# Candunio.net
KiCad netlist of a schematic drawn in Altium Designer
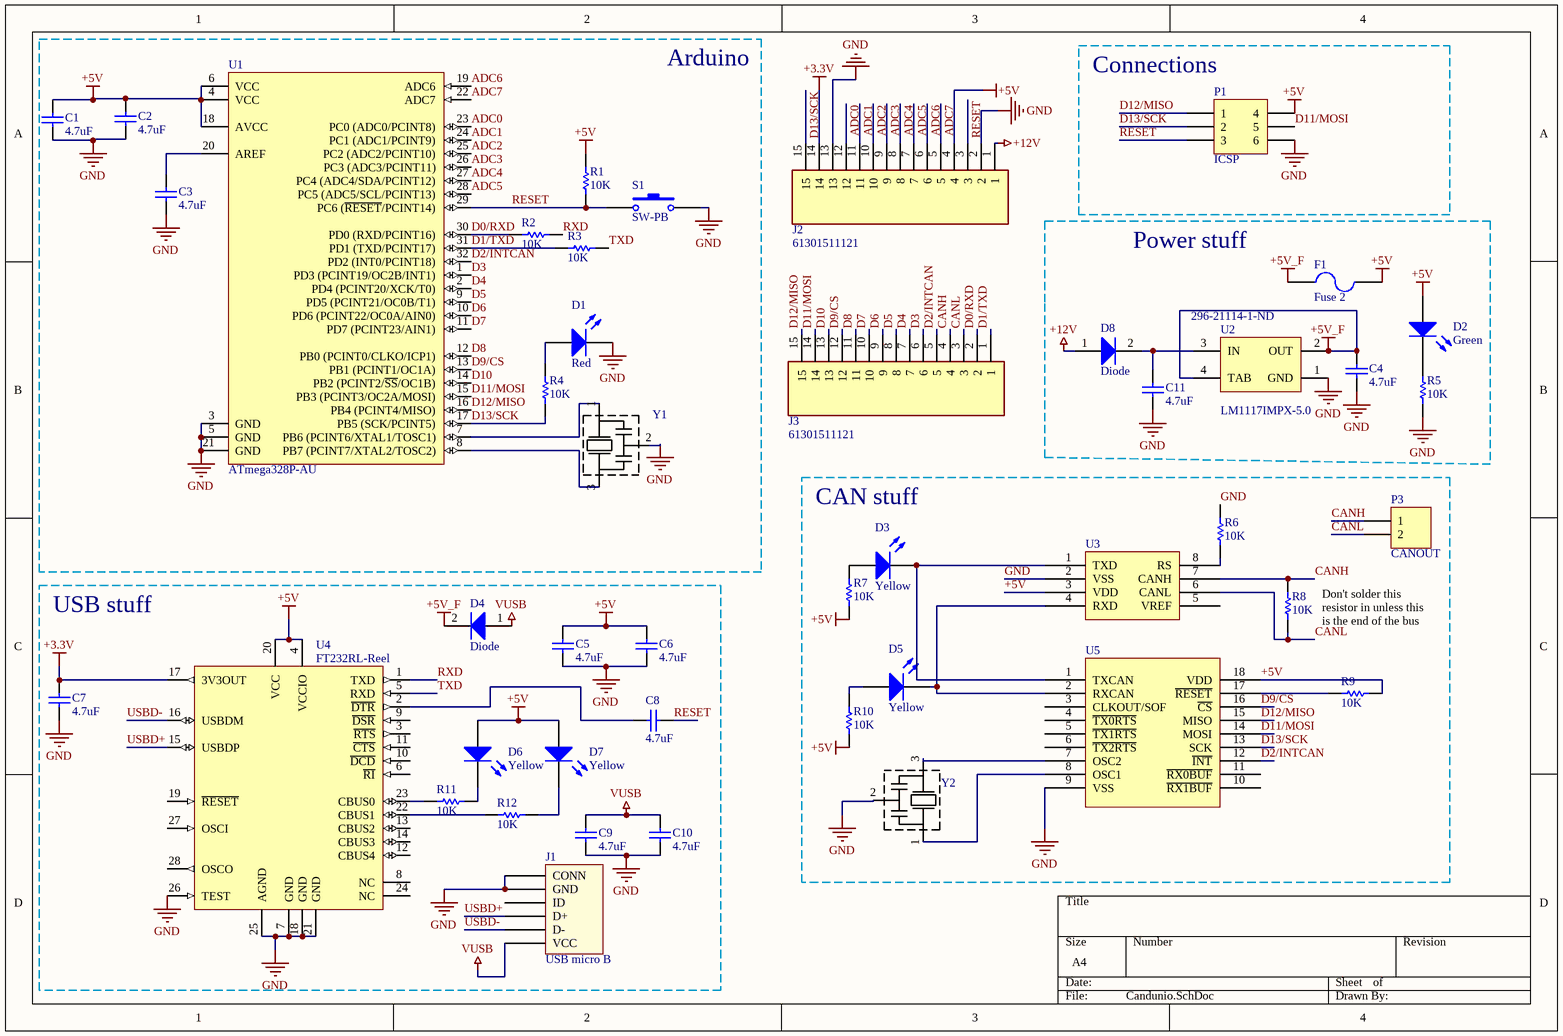
[diagram p0: Candunio.SchDoc]

(export (version "E")
  (design (tool "Eeschema 10.0.6"))
  (components
    (comp (ref "C1")
      (value "4.7uF")
      (footprint "CAPC3216X170N")
      (description "Capacitor (Semiconductor SIM Model)")
      (fields
        (field (name "MANUFACTURER") "Murata")
        (field (name "MANUFACTURER PART NUMBER") "GRM31MR71H105KA88L")
        (field (name "PUBLISHER") "Altium Limited")
      )
      (libsource (lib "Candunio") (part "Cap Semi"))
    )
    (comp (ref "C2")
      (value "4.7uF")
      (footprint "CAPC3216X170N")
      (description "Capacitor (Semiconductor SIM Model)")
      (fields
        (field (name "MANUFACTURER") "Murata")
        (field (name "MANUFACTURER PART NUMBER") "GRM31MR71H105KA88L")
        (field (name "PUBLISHER") "Altium Limited")
      )
      (libsource (lib "Candunio") (part "Cap Semi"))
    )
    (comp (ref "C3")
      (value "4.7uF")
      (footprint "CAPC3216X170N")
      (description "Capacitor (Semiconductor SIM Model)")
      (fields
        (field (name "MANUFACTURER") "Murata")
        (field (name "MANUFACTURER PART NUMBER") "GRM31MR71H105KA88L")
        (field (name "PUBLISHER") "Altium Limited")
      )
      (libsource (lib "Candunio") (part "Cap Semi"))
    )
    (comp (ref "C4")
      (value "4.7uF")
      (footprint "CAPC3216X170N")
      (description "Capacitor (Semiconductor SIM Model)")
      (fields
        (field (name "MANUFACTURER") "Murata")
        (field (name "MANUFACTURER PART NUMBER") "GRM31MR71H105KA88L")
        (field (name "PUBLISHER") "Altium Limited")
      )
      (libsource (lib "Candunio") (part "Cap Semi"))
    )
    (comp (ref "C5")
      (value "4.7uF")
      (footprint "CAPC3216X170N")
      (description "Capacitor (Semiconductor SIM Model)")
      (fields
        (field (name "MANUFACTURER") "Murata")
        (field (name "MANUFACTURER PART NUMBER") "GRM31MR71H105KA88L")
        (field (name "PUBLISHER") "Altium Limited")
      )
      (libsource (lib "Candunio") (part "Cap Semi"))
    )
    (comp (ref "C6")
      (value "4.7uF")
      (footprint "CAPC3216X170N")
      (description "Capacitor (Semiconductor SIM Model)")
      (fields
        (field (name "MANUFACTURER") "Murata")
        (field (name "MANUFACTURER PART NUMBER") "GRM31MR71H105KA88L")
        (field (name "PUBLISHER") "Altium Limited")
      )
      (libsource (lib "Candunio") (part "Cap Semi"))
    )
    (comp (ref "C7")
      (value "4.7uF")
      (footprint "CAPC3216X170N")
      (description "Capacitor (Semiconductor SIM Model)")
      (fields
        (field (name "MANUFACTURER") "Murata")
        (field (name "MANUFACTURER PART NUMBER") "GRM31MR71H105KA88L")
        (field (name "PUBLISHER") "Altium Limited")
      )
      (libsource (lib "Candunio") (part "Cap Semi"))
    )
    (comp (ref "C8")
      (value "4.7uF")
      (footprint "CAPC3216X170N")
      (description "Capacitor (Semiconductor SIM Model)")
      (fields
        (field (name "MANUFACTURER") "Murata")
        (field (name "MANUFACTURER PART NUMBER") "GRM31MR71H105KA88L")
        (field (name "PUBLISHER") "Altium Limited")
      )
      (libsource (lib "Candunio") (part "Cap Semi"))
    )
    (comp (ref "C9")
      (value "4.7uF")
      (footprint "CAPC3216X170N")
      (description "Capacitor (Semiconductor SIM Model)")
      (fields
        (field (name "MANUFACTURER") "Murata")
        (field (name "MANUFACTURER PART NUMBER") "GRM31MR71H105KA88L")
        (field (name "PUBLISHER") "Altium Limited")
      )
      (libsource (lib "Candunio") (part "Cap Semi"))
    )
    (comp (ref "C10")
      (value "4.7uF")
      (footprint "CAPC3216X170N")
      (description "Capacitor (Semiconductor SIM Model)")
      (fields
        (field (name "MANUFACTURER") "Murata")
        (field (name "MANUFACTURER PART NUMBER") "GRM31MR71H105KA88L")
        (field (name "PUBLISHER") "Altium Limited")
      )
      (libsource (lib "Candunio") (part "Cap Semi"))
    )
    (comp (ref "C11")
      (value "4.7uF")
      (footprint "CAPC3216X170N")
      (description "Capacitor (Semiconductor SIM Model)")
      (fields
        (field (name "MANUFACTURER") "Murata")
        (field (name "MANUFACTURER PART NUMBER") "GRM31MR71H105KA88L")
        (field (name "PUBLISHER") "Altium Limited")
      )
      (libsource (lib "Candunio") (part "Cap Semi"))
    )
    (comp (ref "D1")
      (value "Red")
      (footprint "LEDC3216X120NRED")
      (description "Typical RED, GREEN, YELLOW, AMBER GaAs LED")
      (fields
        (field (name "MANUFACTURER") "Broadcom Avago")
        (field (name "MANUFACTURER PART NUMBER") "HSMY-C150")
        (field (name "PUBLISHER") "Altium Limited")
      )
      (libsource (lib "Candunio") (part "LED2_2"))
    )
    (comp (ref "D2")
      (value "Green")
      (footprint "LEDC3216X120NGRN")
      (description "Typical RED, GREEN, YELLOW, AMBER GaAs LED")
      (fields
        (field (name "MANUFACTURER") "Broadcom Avago")
        (field (name "MANUFACTURER PART NUMBER") "HSMG-C150")
        (field (name "PUBLISHER") "Altium Limited")
      )
      (libsource (lib "Candunio") (part "LED2"))
    )
    (comp (ref "D3")
      (value "Yellow")
      (footprint "LEDC3216X120NYEL")
      (description "Typical RED, GREEN, YELLOW, AMBER GaAs LED")
      (fields
        (field (name "MANUFACTURER") "Broadcom Avago")
        (field (name "MANUFACTURER PART NUMBER") "HSMY-C150")
        (field (name "PUBLISHER") "Altium Limited")
      )
      (libsource (lib "Candunio") (part "LED2_1"))
    )
    (comp (ref "D4")
      (value "Diode")
      (footprint "DO-220AA")
      (description "Default Diode")
      (fields (field (name "PUBLISHER") "Altium Limited"))
      (libsource (lib "Candunio") (part "Diode"))
    )
    (comp (ref "D5")
      (value "Yellow")
      (footprint "LEDC3216X120NYEL")
      (description "Typical RED, GREEN, YELLOW, AMBER GaAs LED")
      (fields
        (field (name "MANUFACTURER") "Broadcom Avago")
        (field (name "MANUFACTURER PART NUMBER") "HSMY-C150")
        (field (name "PUBLISHER") "Altium Limited")
      )
      (libsource (lib "Candunio") (part "LED2_1"))
    )
    (comp (ref "D6")
      (value "Yellow")
      (footprint "LEDC3216X120NYEL")
      (description "Typical RED, GREEN, YELLOW, AMBER GaAs LED")
      (fields
        (field (name "MANUFACTURER") "Broadcom Avago")
        (field (name "MANUFACTURER PART NUMBER") "HSMY-C150")
        (field (name "PUBLISHER") "Altium Limited")
      )
      (libsource (lib "Candunio") (part "LED2_1"))
    )
    (comp (ref "D7")
      (value "Yellow")
      (footprint "LEDC3216X120NYEL")
      (description "Typical RED, GREEN, YELLOW, AMBER GaAs LED")
      (fields
        (field (name "MANUFACTURER") "Broadcom Avago")
        (field (name "MANUFACTURER PART NUMBER") "HSMY-C150")
        (field (name "PUBLISHER") "Altium Limited")
      )
      (libsource (lib "Candunio") (part "LED2_1"))
    )
    (comp (ref "D8")
      (value "Diode")
      (footprint "DO-220AA")
      (description "Default Diode")
      (fields (field (name "PUBLISHER") "Altium Limited"))
      (libsource (lib "Candunio") (part "Diode"))
    )
    (comp (ref "F1")
      (value "Fuse 2")
      (footprint "FUSC4632X85N")
      (description "Fuse")
      (fields
        (field (name "PART NUMBER") "MF-MSMF050-2")
        (field (name "MANUFACTURER") "Bourns")
        (field (name "PUBLISHER") "Altium Limited")
      )
      (libsource (lib "Candunio") (part "Fuse 2"))
    )
    (comp (ref "J1")
      (value "USB micro B")
      (footprint "1050170001")
      (description "CONN SM TH USB MICRO MODIFIED FOR DRILL")
      (fields (field (name "PART NUMBER") "WM1399CT-ND"))
      (libsource (lib "electronpowered") (part "1050170001"))
    )
    (comp (ref "J2")
      (value "61301511121")
      (footprint "SamacSys:HDRV15W95P0X254_1X15_3810X254X854P")
      (description "Connector")
      (fields
        (field (name "MOUSER PART NUMBER") "710-61301511121")
        (field (name "RS PART NUMBER") "8281623P")
      )
      (libsource (lib "*") (part "61301511121"))
    )
    (comp (ref "J3")
      (value "61301511121")
      (footprint "SamacSys:HDRV15W95P0X254_1X15_3810X254X854P")
      (description "Connector")
      (fields
        (field (name "MOUSER PART NUMBER") "710-61301511121")
        (field (name "RS PART NUMBER") "8281623P")
      )
      (libsource (lib "*") (part "61301511121"))
    )
    (comp (ref "P1")
      (value "ICSP")
      (footprint "Pin Header 2x3 TH Pitch 2.54mm")
      (description "Header, 3-Pin, Dual row")
      (fields (field (name "PUBLISHER") "Altium Limited"))
      (libsource (lib "Candunio") (part "Header 3X2A"))
    )
    (comp (ref "P3")
      (value "CANOUT")
      (footprint "Pin Header 1x2 TH Pitch 2.54mm")
      (description "Header, 2-Pin")
      (fields (field (name "PUBLISHER") "Altium Limited"))
      (libsource (lib "Candunio") (part "Header 2"))
    )
    (comp (ref "R1")
      (value "10K")
      (footprint "RESC3216X60N")
      (description "Resistor")
      (fields
        (field (name "MANUFACTURER") "Stackpole Electronics")
        (field (name "MANUFACTURER PART NUMBER") "RNCP1206FTD1K00")
      )
      (libsource (lib "Candunio") (part "Res1"))
    )
    (comp (ref "R2")
      (value "10K")
      (footprint "RESC3216X60N")
      (description "Resistor")
      (fields
        (field (name "MANUFACTURER") "Stackpole Electronics")
        (field (name "MANUFACTURER PART NUMBER") "RNCP1206FTD1K00")
      )
      (libsource (lib "Candunio") (part "Res1"))
    )
    (comp (ref "R3")
      (value "10K")
      (footprint "RESC3216X60N")
      (description "Resistor")
      (fields
        (field (name "MANUFACTURER") "Stackpole Electronics")
        (field (name "MANUFACTURER PART NUMBER") "RNCP1206FTD1K00")
      )
      (libsource (lib "Candunio") (part "Res1"))
    )
    (comp (ref "R4")
      (value "10K")
      (footprint "RESC3216X60N")
      (description "Resistor")
      (fields
        (field (name "MANUFACTURER") "Stackpole Electronics")
        (field (name "MANUFACTURER PART NUMBER") "RNCP1206FTD1K00")
      )
      (libsource (lib "Candunio") (part "Res1"))
    )
    (comp (ref "R5")
      (value "10K")
      (footprint "RESC3216X60N")
      (description "Resistor")
      (fields
        (field (name "MANUFACTURER") "Stackpole Electronics")
        (field (name "MANUFACTURER PART NUMBER") "RNCP1206FTD1K00")
      )
      (libsource (lib "Candunio") (part "Res1"))
    )
    (comp (ref "R6")
      (value "10K")
      (footprint "RESC3216X60N")
      (description "Resistor")
      (fields
        (field (name "MANUFACTURER") "Stackpole Electronics")
        (field (name "MANUFACTURER PART NUMBER") "RNCP1206FTD1K00")
      )
      (libsource (lib "Candunio") (part "Res1"))
    )
    (comp (ref "R7")
      (value "10K")
      (footprint "RESC3216X60N")
      (description "Resistor")
      (fields
        (field (name "MANUFACTURER") "Stackpole Electronics")
        (field (name "MANUFACTURER PART NUMBER") "RNCP1206FTD1K00")
      )
      (libsource (lib "Candunio") (part "Res1"))
    )
    (comp (ref "R8")
      (value "10K")
      (footprint "RESC3216X60N")
      (description "Resistor")
      (fields
        (field (name "MANUFACTURER") "Stackpole Electronics")
        (field (name "MANUFACTURER PART NUMBER") "RNCP1206FTD1K00")
      )
      (libsource (lib "Candunio") (part "Res1"))
    )
    (comp (ref "R9")
      (value "10K")
      (footprint "RESC3216X60N")
      (description "Resistor")
      (fields
        (field (name "MANUFACTURER") "Stackpole Electronics")
        (field (name "MANUFACTURER PART NUMBER") "RNCP1206FTD1K00")
      )
      (libsource (lib "Candunio") (part "Res1"))
    )
    (comp (ref "R10")
      (value "10K")
      (footprint "RESC3216X60N")
      (description "Resistor")
      (fields
        (field (name "MANUFACTURER") "Stackpole Electronics")
        (field (name "MANUFACTURER PART NUMBER") "RNCP1206FTD1K00")
      )
      (libsource (lib "Candunio") (part "Res1"))
    )
    (comp (ref "R11")
      (value "10K")
      (footprint "RESC3216X60N")
      (description "Resistor")
      (fields
        (field (name "MANUFACTURER") "Stackpole Electronics")
        (field (name "MANUFACTURER PART NUMBER") "RNCP1206FTD1K00")
      )
      (libsource (lib "Candunio") (part "Res1"))
    )
    (comp (ref "R12")
      (value "10K")
      (footprint "RESC3216X60N")
      (description "Resistor")
      (fields
        (field (name "MANUFACTURER") "Stackpole Electronics")
        (field (name "MANUFACTURER PART NUMBER") "RNCP1206FTD1K00")
      )
      (libsource (lib "Candunio") (part "Res1"))
    )
    (comp (ref "S1")
      (value "SW-PB")
      (footprint "SMDswitch_1206")
      (description "Switch")
      (fields
        (field (name "MANUFACTURER") "ITT C&K")
        (field (name "MANUFACTURER PART NUMBER") "KXT331LHS")
        (field (name "PUBLISHER") "Altium Limited")
      )
      (libsource (lib "Candunio") (part "SW-PB"))
    )
    (comp (ref "U1")
      (value "ATmega328P-AU")
      (footprint "QFP80P900X900X120-32N")
      (fields (field (name "PUBLISHER") "Altium Limited"))
      (libsource (lib "Candunio") (part "ATmega328P-AU"))
    )
    (comp (ref "U2")
      (value "LM1117IMPX-5.0")
      (footprint "SOT230P700X180-4N")
      (description "800mA Low-Dropout Linear Regulator, 4-pin SOT-223")
      (fields
        (field (name "PARTNUMBER") "LM1117IMPX-5.0/NOPBCT-ND")
        (field (name "MANUFACTURER") "National Semiconductor")
        (field (name "SUPPLIER PART NUMBER") "296-21114-1-ND")
        (field (name "PUBLISHER") "Altium Limited")
      )
      (libsource (lib "NSC LDO") (part "LM1117IMPX-5.0"))
    )
    (comp (ref "U3")
      (value "MCP2551-E/SN")
      (footprint "SOIC127P600X175-8N")
      (description "SOIC")
      (libsource (lib "Candunio") (part "MCP2551-E/SN"))
    )
    (comp (ref "U4")
      (value "FT232RL-Reel")
      (footprint "SOP65P780X200-28N")
      (description "USB UART Asynchronous Serial Data Transfer Chip, SSOP-28, Tape and Reel")
      (fields
        (field (name "MANUFACTURER") "FTDI")
        (field (name "MANUFACTURER PART NUMBER") "FT232RL-REEL")
        (field (name "PUBLISHER") "Altium Limited")
      )
      (libsource (lib "FTDI Communication UART") (part "FT232RL-Reel"))
    )
    (comp (ref "U5")
      (value "MCP2515-E/ST")
      (footprint "SOIC127P1030X265-18N")
      (description "SOIC")
      (libsource (lib "Candunio") (part "MCP2515-E/ST"))
    )
    (comp (ref "Y1")
      (value "CSTCE16M0V53-R0")
      (footprint "CSTCE_G")
      (fields
        (field (name "MANUFACTURER") "Murata")
        (field (name "MANUFACTURER PART NUMBER") "CSTCE16M0V53C-R0")
        (field (name "TOLERANCE") "0.5%")
      )
      (libsource (lib "Candunio") (part "CSTCE16M0V53-R0"))
    )
    (comp (ref "Y2")
      (value "CSTCE16M0V53-R0")
      (footprint "CSTCE_G")
      (fields
        (field (name "MANUFACTURER") "Murata")
        (field (name "MANUFACTURER PART NUMBER") "CSTCE16M0V53C-R0")
        (field (name "TOLERANCE") "0.5%")
      )
      (libsource (lib "Candunio") (part "CSTCE16M0V53-R0"))
    )
  )
  (nets
    (net (code "1") (name "+3.3V") (class "Default")
      (node (ref "C7") (pin "2") (pinfunction "2_2") (pintype "passive"))
      (node (ref "J2") (pin "14") (pinfunction "14_14") (pintype "passive"))
      (node (ref "U4") (pin "17") (pinfunction "3V3OUT_17") (pintype "output"))
    )
    (net (code "2") (name "+5V") (class "Default")
      (node (ref "C1") (pin "1") (pinfunction "1_1") (pintype "passive"))
      (node (ref "C2") (pin "2") (pinfunction "2_2") (pintype "passive"))
      (node (ref "C5") (pin "2") (pinfunction "2_2") (pintype "passive"))
      (node (ref "C6") (pin "2") (pinfunction "2_2") (pintype "passive"))
      (node (ref "D2") (pin "2") (pinfunction "A_2") (pintype "passive"))
      (node (ref "D6") (pin "2") (pinfunction "A_2") (pintype "passive"))
      (node (ref "D7") (pin "2") (pinfunction "A_2") (pintype "passive"))
      (node (ref "F1") (pin "2") (pinfunction "2_2") (pintype "passive"))
      (node (ref "J2") (pin "4") (pinfunction "4_4") (pintype "passive"))
      (node (ref "P1") (pin "4") (pinfunction "4_4") (pintype "passive"))
      (node (ref "R1") (pin "1") (pinfunction "1_1") (pintype "passive"))
      (node (ref "R10") (pin "2") (pinfunction "2_2") (pintype "passive"))
      (node (ref "R7") (pin "1") (pinfunction "1_1") (pintype "passive"))
      (node (ref "R9") (pin "2") (pinfunction "2_2") (pintype "passive"))
      (node (ref "U1") (pin "18") (pinfunction "AVCC_18") (pintype "power_in"))
      (node (ref "U1") (pin "4") (pinfunction "VCC_4") (pintype "power_in"))
      (node (ref "U1") (pin "6") (pinfunction "VCC_6") (pintype "power_in"))
      (node (ref "U3") (pin "3") (pinfunction "VDD_3") (pintype "passive"))
      (node (ref "U4") (pin "20") (pinfunction "VCC_20") (pintype "power_in"))
      (node (ref "U4") (pin "4") (pinfunction "VCCIO_4") (pintype "power_in"))
      (node (ref "U5") (pin "18") (pinfunction "VDD_18") (pintype "passive"))
    )
    (net (code "3") (name "+5V_F") (class "Default")
      (node (ref "C4") (pin "2") (pinfunction "2_2") (pintype "passive"))
      (node (ref "D4") (pin "2") (pinfunction "K_2") (pintype "passive"))
      (node (ref "F1") (pin "1") (pinfunction "1_1") (pintype "passive"))
      (node (ref "U2") (pin "2") (pinfunction "OUT_2") (pintype "power_in"))
      (node (ref "U2") (pin "4") (pinfunction "TAB_4") (pintype "power_in"))
    )
    (net (code "4") (name "+12V") (class "Default")
      (node (ref "D8") (pin "1") (pinfunction "A_1") (pintype "passive"))
      (node (ref "J2") (pin "1") (pinfunction "1_1") (pintype "passive"))
    )
    (net (code "5") (name "/ADC0") (class "Default")
      (node (ref "J2") (pin "12") (pinfunction "12_12") (pintype "passive"))
      (node (ref "U1") (pin "23") (pinfunction "PC0_(ADC0/PCINT8)_23") (pintype "bidirectional"))
    )
    (net (code "6") (name "/ADC1") (class "Default")
      (node (ref "J2") (pin "11") (pinfunction "11_11") (pintype "passive"))
      (node (ref "U1") (pin "24") (pinfunction "PC1_(ADC1/PCINT9)_24") (pintype "bidirectional"))
    )
    (net (code "7") (name "/ADC2") (class "Default")
      (node (ref "J2") (pin "10") (pinfunction "10_10") (pintype "passive"))
      (node (ref "U1") (pin "25") (pinfunction "PC2_(ADC2/PCINT10)_25") (pintype "bidirectional"))
    )
    (net (code "8") (name "/ADC3") (class "Default")
      (node (ref "J2") (pin "9") (pinfunction "9_9") (pintype "passive"))
      (node (ref "U1") (pin "26") (pinfunction "PC3_(ADC3/PCINT11)_26") (pintype "bidirectional"))
    )
    (net (code "9") (name "/ADC4") (class "Default")
      (node (ref "J2") (pin "8") (pinfunction "8_8") (pintype "passive"))
      (node (ref "U1") (pin "27") (pinfunction "PC4_(ADC4/SDA/PCINT12)_27") (pintype "bidirectional"))
    )
    (net (code "10") (name "/ADC5") (class "Default")
      (node (ref "J2") (pin "7") (pinfunction "7_7") (pintype "passive"))
      (node (ref "U1") (pin "28") (pinfunction "PC5_(ADC5/SCL/PCINT13)_28") (pintype "bidirectional"))
    )
    (net (code "11") (name "/ADC6") (class "Default")
      (node (ref "J2") (pin "6") (pinfunction "6_6") (pintype "passive"))
      (node (ref "U1") (pin "19") (pinfunction "ADC6_19") (pintype "input"))
    )
    (net (code "12") (name "/ADC7") (class "Default")
      (node (ref "J2") (pin "5") (pinfunction "5_5") (pintype "passive"))
      (node (ref "U1") (pin "22") (pinfunction "ADC7_22") (pintype "input"))
    )
    (net (code "13") (name "/CANH") (class "Default")
      (node (ref "J3") (pin "4") (pinfunction "4_4") (pintype "passive"))
      (node (ref "P3") (pin "1") (pinfunction "1_1") (pintype "passive"))
      (node (ref "R8") (pin "1") (pinfunction "1_1") (pintype "passive"))
      (node (ref "U3") (pin "7") (pinfunction "CANH_7") (pintype "passive"))
    )
    (net (code "14") (name "/CANL") (class "Default")
      (node (ref "J3") (pin "3") (pinfunction "3_3") (pintype "passive"))
      (node (ref "P3") (pin "2") (pinfunction "2_2") (pintype "passive"))
      (node (ref "R8") (pin "2") (pinfunction "2_2") (pintype "passive"))
      (node (ref "U3") (pin "6") (pinfunction "CANL_6") (pintype "passive"))
    )
    (net (code "15") (name "/D0{slash}RXD") (class "Default")
      (node (ref "J3") (pin "2") (pinfunction "2_2") (pintype "passive"))
      (node (ref "R2") (pin "1") (pinfunction "1_1") (pintype "passive"))
      (node (ref "U1") (pin "30") (pinfunction "PD0_(RXD/PCINT16)_30") (pintype "bidirectional"))
    )
    (net (code "16") (name "/D1{slash}TXD") (class "Default")
      (node (ref "J3") (pin "1") (pinfunction "1_1") (pintype "passive"))
      (node (ref "R3") (pin "1") (pinfunction "1_1") (pintype "passive"))
      (node (ref "U1") (pin "31") (pinfunction "PD1_(TXD/PCINT17)_31") (pintype "bidirectional"))
    )
    (net (code "17") (name "/D2{slash}INTCAN") (class "Default")
      (node (ref "J3") (pin "5") (pinfunction "5_5") (pintype "passive"))
      (node (ref "U1") (pin "32") (pinfunction "PD2_(INT0/PCINT18)_32") (pintype "bidirectional"))
      (node (ref "U5") (pin "12") (pinfunction "~{INT}_12") (pintype "passive"))
    )
    (net (code "18") (name "/D3") (class "Default")
      (node (ref "J3") (pin "6") (pinfunction "6_6") (pintype "passive"))
      (node (ref "U1") (pin "1") (pinfunction "PD3_(PCINT19/OC2B/INT1)_1") (pintype "bidirectional"))
    )
    (net (code "19") (name "/D4") (class "Default")
      (node (ref "J3") (pin "7") (pinfunction "7_7") (pintype "passive"))
      (node (ref "U1") (pin "2") (pinfunction "PD4_(PCINT20/XCK/T0)_2") (pintype "bidirectional"))
    )
    (net (code "20") (name "/D5") (class "Default")
      (node (ref "J3") (pin "8") (pinfunction "8_8") (pintype "passive"))
      (node (ref "U1") (pin "9") (pinfunction "PD5_(PCINT21/OC0B/T1)_9") (pintype "bidirectional"))
    )
    (net (code "21") (name "/D6") (class "Default")
      (node (ref "J3") (pin "9") (pinfunction "9_9") (pintype "passive"))
      (node (ref "U1") (pin "10") (pinfunction "PD6_(PCINT22/OC0A/AIN0)_10") (pintype "bidirectional"))
    )
    (net (code "22") (name "/D7") (class "Default")
      (node (ref "J3") (pin "10") (pinfunction "10_10") (pintype "passive"))
      (node (ref "U1") (pin "11") (pinfunction "PD7_(PCINT23/AIN1)_11") (pintype "bidirectional"))
    )
    (net (code "23") (name "/D8") (class "Default")
      (node (ref "J3") (pin "11") (pinfunction "11_11") (pintype "passive"))
      (node (ref "U1") (pin "12") (pinfunction "PB0_(PCINT0/CLKO/ICP1)_12") (pintype "bidirectional"))
    )
    (net (code "24") (name "/D9{slash}CS") (class "Default")
      (node (ref "J3") (pin "12") (pinfunction "12_12") (pintype "passive"))
      (node (ref "U1") (pin "13") (pinfunction "PB1_(PCINT1/OC1A)_13") (pintype "bidirectional"))
      (node (ref "U5") (pin "16") (pinfunction "~{CS}_16") (pintype "passive"))
    )
    (net (code "25") (name "/D10") (class "Default")
      (node (ref "J3") (pin "13") (pinfunction "13_13") (pintype "passive"))
      (node (ref "U1") (pin "14") (pinfunction "PB2_(PCINT2/~{SS}/OC1B)_14") (pintype "bidirectional"))
    )
    (net (code "26") (name "/D11{slash}MOSI") (class "Default")
      (node (ref "J3") (pin "14") (pinfunction "14_14") (pintype "passive"))
      (node (ref "P1") (pin "5") (pinfunction "5_5") (pintype "passive"))
      (node (ref "U1") (pin "15") (pinfunction "PB3_(PCINT3/OC2A/MOSI)_15") (pintype "bidirectional"))
      (node (ref "U5") (pin "14") (pinfunction "MOSI_14") (pintype "passive"))
    )
    (net (code "27") (name "/D12{slash}MISO") (class "Default")
      (node (ref "J3") (pin "15") (pinfunction "15_15") (pintype "passive"))
      (node (ref "P1") (pin "1") (pinfunction "1_1") (pintype "passive"))
      (node (ref "U1") (pin "16") (pinfunction "PB4_(PCINT4/MISO)_16") (pintype "bidirectional"))
      (node (ref "U5") (pin "15") (pinfunction "MISO_15") (pintype "passive"))
    )
    (net (code "28") (name "/D13{slash}SCK") (class "Default")
      (node (ref "J2") (pin "15") (pinfunction "15_15") (pintype "passive"))
      (node (ref "P1") (pin "2") (pinfunction "2_2") (pintype "passive"))
      (node (ref "R4") (pin "2") (pinfunction "2_2") (pintype "passive"))
      (node (ref "U1") (pin "17") (pinfunction "PB5_(SCK/PCINT5)_17") (pintype "bidirectional"))
      (node (ref "U5") (pin "13") (pinfunction "SCK_13") (pintype "passive"))
    )
    (net (code "29") (name "/RESET") (class "Default")
      (node (ref "C8") (pin "2") (pinfunction "2_2") (pintype "passive"))
      (node (ref "J2") (pin "3") (pinfunction "3_3") (pintype "passive"))
      (node (ref "P1") (pin "3") (pinfunction "3_3") (pintype "passive"))
      (node (ref "R1") (pin "2") (pinfunction "2_2") (pintype "passive"))
      (node (ref "S1") (pin "1") (pinfunction "1_1") (pintype "passive"))
      (node (ref "U1") (pin "29") (pinfunction "PC6_(~{RESET}/PCINT14)_29") (pintype "bidirectional"))
    )
    (net (code "30") (name "/RXD") (class "Default")
      (node (ref "R2") (pin "2") (pinfunction "2_2") (pintype "passive"))
      (node (ref "U4") (pin "1") (pinfunction "TXD_1") (pintype "output"))
    )
    (net (code "31") (name "/TXD") (class "Default")
      (node (ref "R3") (pin "2") (pinfunction "2_2") (pintype "passive"))
      (node (ref "U4") (pin "5") (pinfunction "RXD_5") (pintype "input"))
    )
    (net (code "32") (name "/USBD+") (class "Default")
      (node (ref "J1") (pin "3") (pinfunction "D+_3") (pintype "passive"))
      (node (ref "U4") (pin "15") (pinfunction "USBDP_15") (pintype "bidirectional"))
    )
    (net (code "33") (name "/USBD-") (class "Default")
      (node (ref "J1") (pin "2") (pinfunction "D-_2") (pintype "passive"))
      (node (ref "U4") (pin "16") (pinfunction "USBDM_16") (pintype "bidirectional"))
    )
    (net (code "34") (name "GND") (class "Default")
      (node (ref "C1") (pin "2") (pinfunction "2_2") (pintype "passive"))
      (node (ref "C10") (pin "1") (pinfunction "1_1") (pintype "passive"))
      (node (ref "C11") (pin "1") (pinfunction "1_1") (pintype "passive"))
      (node (ref "C2") (pin "1") (pinfunction "1_1") (pintype "passive"))
      (node (ref "C3") (pin "1") (pinfunction "1_1") (pintype "passive"))
      (node (ref "C4") (pin "1") (pinfunction "1_1") (pintype "passive"))
      (node (ref "C5") (pin "1") (pinfunction "1_1") (pintype "passive"))
      (node (ref "C6") (pin "1") (pinfunction "1_1") (pintype "passive"))
      (node (ref "C7") (pin "1") (pinfunction "1_1") (pintype "passive"))
      (node (ref "C9") (pin "1") (pinfunction "1_1") (pintype "passive"))
      (node (ref "D1") (pin "1") (pinfunction "K_1") (pintype "passive"))
      (node (ref "J1") (pin "0") (pinfunction "CONN_0") (pintype "passive"))
      (node (ref "J1") (pin "5") (pinfunction "GND_5") (pintype "passive"))
      (node (ref "J2") (pin "13") (pinfunction "13_13") (pintype "passive"))
      (node (ref "J2") (pin "2") (pinfunction "2_2") (pintype "passive"))
      (node (ref "P1") (pin "6") (pinfunction "6_6") (pintype "passive"))
      (node (ref "R5") (pin "2") (pinfunction "2_2") (pintype "passive"))
      (node (ref "R6") (pin "1") (pinfunction "1_1") (pintype "passive"))
      (node (ref "S1") (pin "2") (pinfunction "2_2") (pintype "passive"))
      (node (ref "U1") (pin "21") (pinfunction "GND_21") (pintype "power_in"))
      (node (ref "U1") (pin "3") (pinfunction "GND_3") (pintype "power_in"))
      (node (ref "U1") (pin "5") (pinfunction "GND_5") (pintype "power_in"))
      (node (ref "U2") (pin "1") (pinfunction "GND_1") (pintype "power_in"))
      (node (ref "U3") (pin "2") (pinfunction "VSS_2") (pintype "passive"))
      (node (ref "U4") (pin "18") (pinfunction "GND_18") (pintype "power_in"))
      (node (ref "U4") (pin "21") (pinfunction "GND_21") (pintype "power_in"))
      (node (ref "U4") (pin "25") (pinfunction "AGND_25") (pintype "power_in"))
      (node (ref "U4") (pin "26") (pinfunction "TEST_26") (pintype "input"))
      (node (ref "U4") (pin "7") (pinfunction "GND_7") (pintype "power_in"))
      (node (ref "U5") (pin "9") (pinfunction "VSS_9") (pintype "passive"))
      (node (ref "Y1") (pin "2") (pinfunction "2_2") (pintype "passive"))
      (node (ref "Y2") (pin "2") (pinfunction "2_2") (pintype "passive"))
    )
    (net (code "35") (name "Net-(D1-A)") (class "Default")
      (node (ref "D1") (pin "2") (pinfunction "A_2") (pintype "passive"))
      (node (ref "R4") (pin "1") (pinfunction "1_1") (pintype "passive"))
    )
    (net (code "36") (name "Net-(D2-K)") (class "Default")
      (node (ref "D2") (pin "1") (pinfunction "K_1") (pintype "passive"))
      (node (ref "R5") (pin "1") (pinfunction "1_1") (pintype "passive"))
    )
    (net (code "37") (name "Net-(D3-A)") (class "Default")
      (node (ref "D3") (pin "2") (pinfunction "A_2") (pintype "passive"))
      (node (ref "R7") (pin "2") (pinfunction "2_2") (pintype "passive"))
    )
    (net (code "38") (name "Net-(D3-K)") (class "Default")
      (node (ref "D3") (pin "1") (pinfunction "K_1") (pintype "passive"))
      (node (ref "U3") (pin "1") (pinfunction "TXD_1") (pintype "passive"))
      (node (ref "U5") (pin "1") (pinfunction "TXCAN_1") (pintype "passive"))
    )
    (net (code "39") (name "Net-(D5-A)") (class "Default")
      (node (ref "D5") (pin "2") (pinfunction "A_2") (pintype "passive"))
      (node (ref "R10") (pin "1") (pinfunction "1_1") (pintype "passive"))
    )
    (net (code "40") (name "Net-(D5-K)") (class "Default")
      (node (ref "D5") (pin "1") (pinfunction "K_1") (pintype "passive"))
      (node (ref "U3") (pin "4") (pinfunction "RXD_4") (pintype "passive"))
      (node (ref "U5") (pin "2") (pinfunction "RXCAN_2") (pintype "passive"))
    )
    (net (code "41") (name "Net-(D6-K)") (class "Default")
      (node (ref "D6") (pin "1") (pinfunction "K_1") (pintype "passive"))
      (node (ref "R11") (pin "2") (pinfunction "2_2") (pintype "passive"))
    )
    (net (code "42") (name "Net-(D7-K)") (class "Default")
      (node (ref "D7") (pin "1") (pinfunction "K_1") (pintype "passive"))
      (node (ref "R12") (pin "2") (pinfunction "2_2") (pintype "passive"))
    )
    (net (code "43") (name "Net-(D8-K)") (class "Default")
      (node (ref "C11") (pin "2") (pinfunction "2_2") (pintype "passive"))
      (node (ref "D8") (pin "2") (pinfunction "K_2") (pintype "passive"))
      (node (ref "U2") (pin "3") (pinfunction "IN_3") (pintype "power_in"))
    )
    (net (code "44") (name "Net-(U1-AREF)") (class "Default")
      (node (ref "C3") (pin "2") (pinfunction "2_2") (pintype "passive"))
      (node (ref "U1") (pin "20") (pinfunction "AREF_20") (pintype "passive"))
    )
    (net (code "45") (name "Net-(U1-PB6_(PCINT6{slash}XTAL1{slash}TOSC1))") (class "Default")
      (node (ref "U1") (pin "7") (pinfunction "PB6_(PCINT6/XTAL1/TOSC1)_7") (pintype "bidirectional"))
      (node (ref "Y1") (pin "1") (pinfunction "1_1") (pintype "passive"))
    )
    (net (code "46") (name "Net-(U1-PB7_(PCINT7{slash}XTAL2{slash}TOSC2))") (class "Default")
      (node (ref "U1") (pin "8") (pinfunction "PB7_(PCINT7/XTAL2/TOSC2)_8") (pintype "bidirectional"))
      (node (ref "Y1") (pin "3") (pinfunction "3_3") (pintype "passive"))
    )
    (net (code "47") (name "Net-(U3-RS)") (class "Default")
      (node (ref "R6") (pin "2") (pinfunction "2_2") (pintype "passive"))
      (node (ref "U3") (pin "8") (pinfunction "RS_8") (pintype "passive"))
    )
    (net (code "48") (name "Net-(U4-CBUS0)") (class "Default")
      (node (ref "R11") (pin "1") (pinfunction "1_1") (pintype "passive"))
      (node (ref "U4") (pin "23") (pinfunction "CBUS0_23") (pintype "bidirectional"))
    )
    (net (code "49") (name "Net-(U4-CBUS1)") (class "Default")
      (node (ref "R12") (pin "1") (pinfunction "1_1") (pintype "passive"))
      (node (ref "U4") (pin "22") (pinfunction "CBUS1_22") (pintype "bidirectional"))
    )
    (net (code "50") (name "Net-(U4-~{DTR})") (class "Default")
      (node (ref "C8") (pin "1") (pinfunction "1_1") (pintype "passive"))
      (node (ref "U4") (pin "2") (pinfunction "~{DTR}_2") (pintype "output"))
    )
    (net (code "51") (name "Net-(U5-OSC1)") (class "Default")
      (node (ref "U5") (pin "8") (pinfunction "OSC1_8") (pintype "passive"))
      (node (ref "Y2") (pin "1") (pinfunction "1_1") (pintype "passive"))
    )
    (net (code "52") (name "Net-(U5-OSC2)") (class "Default")
      (node (ref "U5") (pin "7") (pinfunction "OSC2_7") (pintype "passive"))
      (node (ref "Y2") (pin "3") (pinfunction "3_3") (pintype "passive"))
    )
    (net (code "53") (name "Net-(U5-~{RESET})") (class "Default")
      (node (ref "R9") (pin "1") (pinfunction "1_1") (pintype "passive"))
      (node (ref "U5") (pin "17") (pinfunction "~{RESET}_17") (pintype "passive"))
    )
    (net (code "54") (name "VUSB") (class "Default")
      (node (ref "C10") (pin "2") (pinfunction "2_2") (pintype "passive"))
      (node (ref "C9") (pin "2") (pinfunction "2_2") (pintype "passive"))
      (node (ref "D4") (pin "1") (pinfunction "A_1") (pintype "passive"))
      (node (ref "J1") (pin "1") (pinfunction "VCC_1") (pintype "passive"))
    )
    (net (code "55") (name "unconnected-(J1-ID-Pad4)") (class "Default")
      (node (ref "J1") (pin "4") (pinfunction "ID_4") (pintype "passive"))
    )
    (net (code "56") (name "unconnected-(U3-VREF-Pad5)") (class "Default")
      (node (ref "U3") (pin "5") (pinfunction "VREF_5") (pintype "passive"))
    )
    (net (code "57") (name "unconnected-(U4-CBUS2-Pad13)") (class "Default")
      (node (ref "U4") (pin "13") (pinfunction "CBUS2_13") (pintype "bidirectional"))
    )
    (net (code "58") (name "unconnected-(U4-CBUS3-Pad14)") (class "Default")
      (node (ref "U4") (pin "14") (pinfunction "CBUS3_14") (pintype "bidirectional"))
    )
    (net (code "59") (name "unconnected-(U4-CBUS4-Pad12)") (class "Default")
      (node (ref "U4") (pin "12") (pinfunction "CBUS4_12") (pintype "bidirectional"))
    )
    (net (code "60") (name "unconnected-(U4-NC-Pad8)") (class "Default")
      (node (ref "U4") (pin "8") (pinfunction "NC_8") (pintype "passive"))
    )
    (net (code "61") (name "unconnected-(U4-NC-Pad24)") (class "Default")
      (node (ref "U4") (pin "24") (pinfunction "NC_24") (pintype "passive"))
    )
    (net (code "62") (name "unconnected-(U4-OSCI-Pad27)") (class "Default")
      (node (ref "U4") (pin "27") (pinfunction "OSCI_27") (pintype "input"))
    )
    (net (code "63") (name "unconnected-(U4-OSCO-Pad28)") (class "Default")
      (node (ref "U4") (pin "28") (pinfunction "OSCO_28") (pintype "output"))
    )
    (net (code "64") (name "unconnected-(U4-~{CTS}-Pad11)") (class "Default")
      (node (ref "U4") (pin "11") (pinfunction "~{CTS}_11") (pintype "input"))
    )
    (net (code "65") (name "unconnected-(U4-~{DCD}-Pad10)") (class "Default")
      (node (ref "U4") (pin "10") (pinfunction "~{DCD}_10") (pintype "input"))
    )
    (net (code "66") (name "unconnected-(U4-~{DSR}-Pad9)") (class "Default")
      (node (ref "U4") (pin "9") (pinfunction "~{DSR}_9") (pintype "input"))
    )
    (net (code "67") (name "unconnected-(U4-~{RESET}-Pad19)") (class "Default")
      (node (ref "U4") (pin "19") (pinfunction "~{RESET}_19") (pintype "input"))
    )
    (net (code "68") (name "unconnected-(U4-~{RI}-Pad6)") (class "Default")
      (node (ref "U4") (pin "6") (pinfunction "~{RI}_6") (pintype "input"))
    )
    (net (code "69") (name "unconnected-(U4-~{RTS}-Pad3)") (class "Default")
      (node (ref "U4") (pin "3") (pinfunction "~{RTS}_3") (pintype "output"))
    )
    (net (code "70") (name "unconnected-(U5-CLKOUT{slash}SOF-Pad3)") (class "Default")
      (node (ref "U5") (pin "3") (pinfunction "CLKOUT/SOF_3") (pintype "passive"))
    )
    (net (code "71") (name "unconnected-(U5-~{RX0BUF}-Pad11)") (class "Default")
      (node (ref "U5") (pin "11") (pinfunction "~{RX0BUF}_11") (pintype "passive"))
    )
    (net (code "72") (name "unconnected-(U5-~{RX1BUF}-Pad10)") (class "Default")
      (node (ref "U5") (pin "10") (pinfunction "~{RX1BUF}_10") (pintype "passive"))
    )
    (net (code "73") (name "unconnected-(U5-~{TX0RTS}-Pad4)") (class "Default")
      (node (ref "U5") (pin "4") (pinfunction "~{TX0RTS}_4") (pintype "passive"))
    )
    (net (code "74") (name "unconnected-(U5-~{TX1RTS}-Pad5)") (class "Default")
      (node (ref "U5") (pin "5") (pinfunction "~{TX1RTS}_5") (pintype "passive"))
    )
    (net (code "75") (name "unconnected-(U5-~{TX2RTS}-Pad6)") (class "Default")
      (node (ref "U5") (pin "6") (pinfunction "~{TX2RTS}_6") (pintype "passive"))
    )
  )
)
